# ROV_PWR_4inch.net
KiCad netlist of a schematic drawn in EAGLE
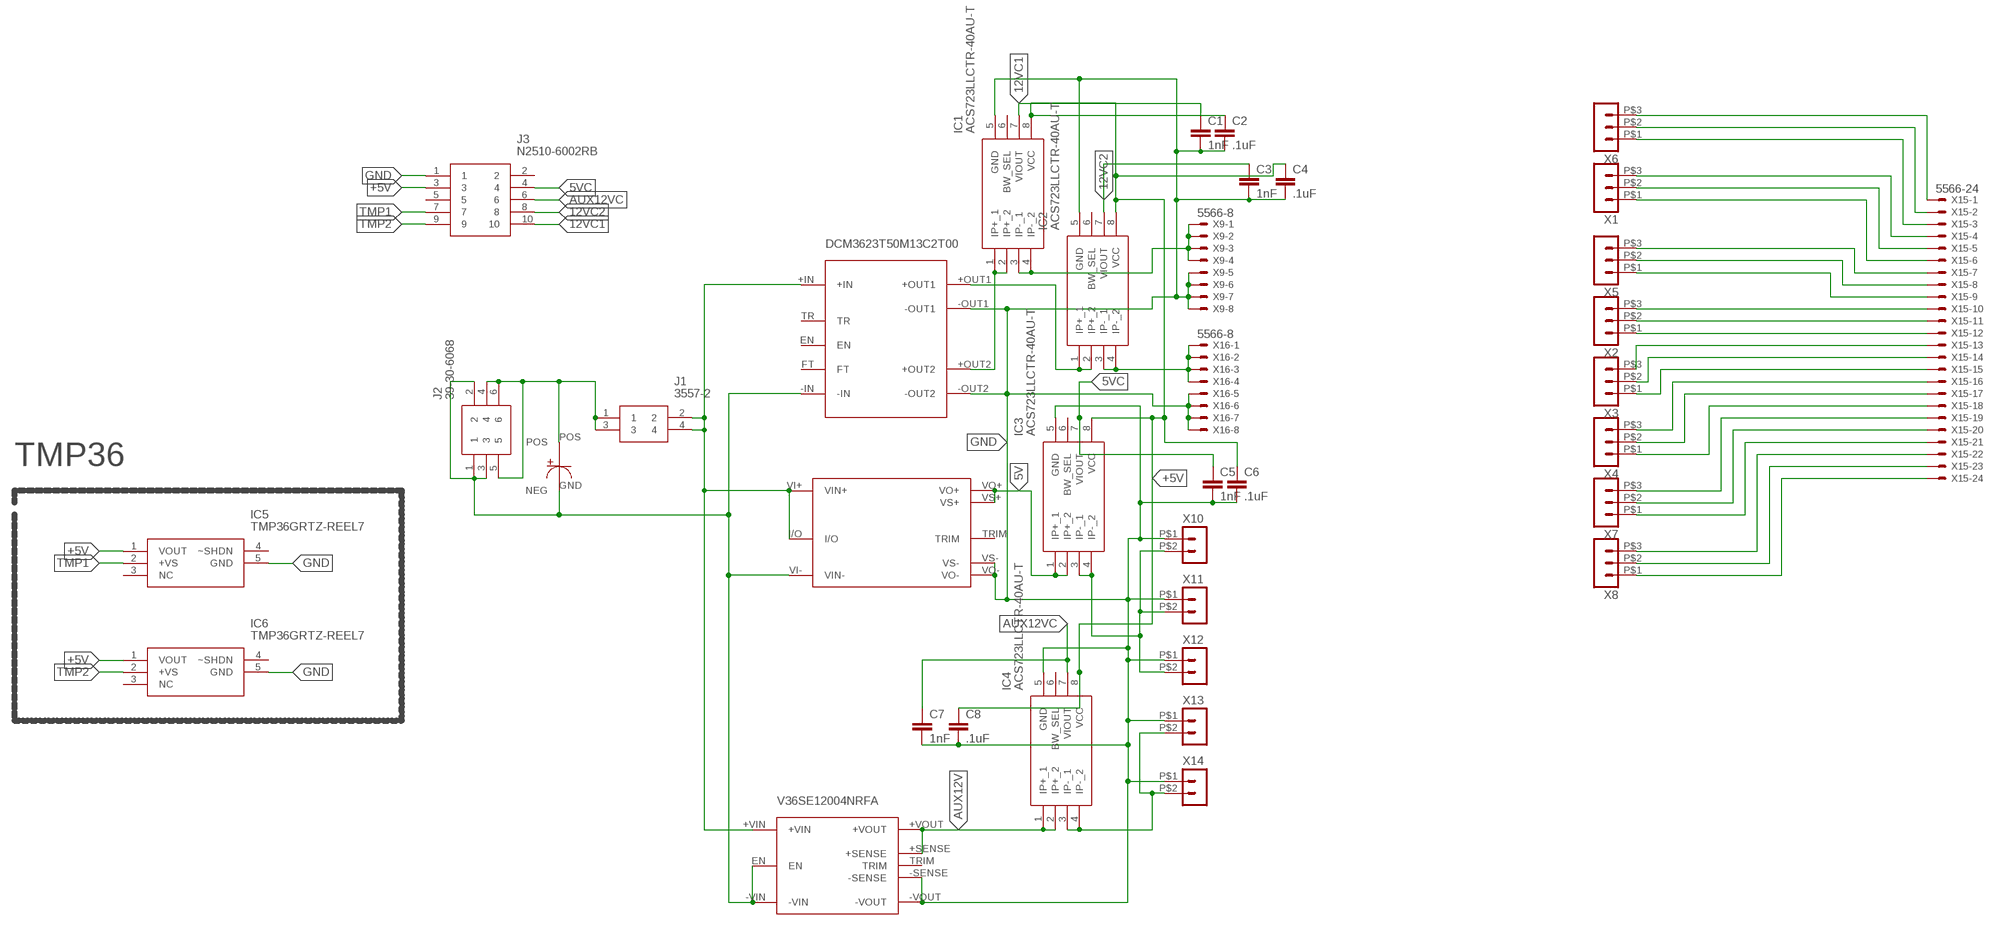
[diagram p0: schematic, sheet 1]

(export (version "E")
  (design (tool "Eeschema 10.0.6"))
  (components
    (comp (ref "C1")
      (value "1nF")
      (footprint "eagle-import:C0402")
      (libsource (lib "eagle-import") (part "C-EUC0402"))
    )
    (comp (ref "C2")
      (value ".1uF")
      (footprint "eagle-import:C0402")
      (libsource (lib "eagle-import") (part "C-EUC0402"))
    )
    (comp (ref "C3")
      (value "1nF")
      (footprint "eagle-import:C0402")
      (libsource (lib "eagle-import") (part "C-EUC0402"))
    )
    (comp (ref "C4")
      (value ".1uF")
      (footprint "eagle-import:C0402")
      (libsource (lib "eagle-import") (part "C-EUC0402"))
    )
    (comp (ref "C5")
      (value "1nF")
      (footprint "eagle-import:C0402")
      (libsource (lib "eagle-import") (part "C-EUC0402"))
    )
    (comp (ref "C6")
      (value ".1uF")
      (footprint "eagle-import:C0402")
      (libsource (lib "eagle-import") (part "C-EUC0402"))
    )
    (comp (ref "C7")
      (value "1nF")
      (footprint "eagle-import:C0402")
      (libsource (lib "eagle-import") (part "C-EUC0402"))
    )
    (comp (ref "C8")
      (value ".1uF")
      (footprint "eagle-import:C0402")
      (libsource (lib "eagle-import") (part "C-EUC0402"))
    )
    (comp (ref "IC1")
      (value "ACS723LLCTR-40AU-T")
      (footprint "eagle-import:SOT127P600X175-8N")
      (libsource (lib "eagle-import") (part "ACS723LLCTR-40AU-T"))
    )
    (comp (ref "IC2")
      (value "ACS723LLCTR-40AU-T")
      (footprint "eagle-import:SOT127P600X175-8N")
      (libsource (lib "eagle-import") (part "ACS723LLCTR-40AU-T"))
    )
    (comp (ref "IC3")
      (value "ACS723LLCTR-40AU-T")
      (footprint "eagle-import:SOT127P600X175-8N")
      (libsource (lib "eagle-import") (part "ACS723LLCTR-40AU-T"))
    )
    (comp (ref "IC4")
      (value "ACS723LLCTR-40AU-T")
      (footprint "eagle-import:SOT127P600X175-8N")
      (libsource (lib "eagle-import") (part "ACS723LLCTR-40AU-T"))
    )
    (comp (ref "IC5")
      (value "TMP36GRTZ-REEL7")
      (footprint "eagle-import:SOT95P280X145-5N")
      (fields (field (name "MOUSER_PART_NUMBER") "584-TMP36GRTZ-R7"))
      (libsource (lib "eagle-import") (part "TMP36GRTZ-REEL7"))
    )
    (comp (ref "IC6")
      (value "TMP36GRTZ-REEL7")
      (footprint "eagle-import:SOT95P280X145-5N")
      (fields (field (name "MOUSER_PART_NUMBER") "584-TMP36GRTZ-R7"))
      (libsource (lib "eagle-import") (part "TMP36GRTZ-REEL7"))
    )
    (comp (ref "J1")
      (value "3557-2")
      (footprint "eagle-import:3557-2")
      (fields (field (name "MOUSER_PART_NUMBER") "534-3557-2"))
      (libsource (lib "eagle-import") (part "3557-2"))
    )
    (comp (ref "J2")
      (value "39-30-6068")
      (footprint "eagle-import:39306068")
      (fields (field (name "MOUSER_PART_NUMBER") "538-39-30-6068"))
      (libsource (lib "eagle-import") (part "39-30-6068"))
    )
    (comp (ref "J3")
      (value "N2510-6002RB")
      (footprint "eagle-import:SHDR10W64P254_2X5_2002X859X100")
      (fields (field (name "MOUSER_PART_NUMBER") "517-N2510-6002RB"))
      (libsource (lib "eagle-import") (part "N2510-6002RB"))
    )
    (comp (ref "U$1")
      (value "DCM3623T50M13C2T00")
      (footprint "eagle-import:DCM3623T50M13C2T00")
      (libsource (lib "eagle-import") (part "DCM3623T50M13C2T00"))
    )
    (comp (ref "U$2")
      (value "KHHD006A0A41Z")
      (footprint "eagle-import:KHHD006A0A41Z")
      (libsource (lib "eagle-import") (part "KHHD006A0A41Z"))
    )
    (comp (ref "U$3")
      (value "V36SE12004NRFA")
      (footprint "eagle-import:V36SE12004NRFA")
      (libsource (lib "eagle-import") (part "V36SE12004NRFA"))
    )
    (comp (ref "U$4")
      (value "UBY1V222MHL")
      (footprint "eagle-import:UBY1V222MHL")
      (libsource (lib "eagle-import") (part "UBY1V222MHL"))
    )
    (comp (ref "X1")
      (value "HEADER_POS3_43650-0315")
      (footprint "eagle-import:43650-0315")
      (libsource (lib "eagle-import") (part "HEADER_POS3_?43650-0315"))
    )
    (comp (ref "X2")
      (value "HEADER_POS3_43650-0315")
      (footprint "eagle-import:43650-0315")
      (libsource (lib "eagle-import") (part "HEADER_POS3_?43650-0315"))
    )
    (comp (ref "X3")
      (value "HEADER_POS3_43650-0315")
      (footprint "eagle-import:43650-0315")
      (libsource (lib "eagle-import") (part "HEADER_POS3_?43650-0315"))
    )
    (comp (ref "X4")
      (value "HEADER_POS3_43650-0315")
      (footprint "eagle-import:43650-0315")
      (libsource (lib "eagle-import") (part "HEADER_POS3_?43650-0315"))
    )
    (comp (ref "X5")
      (value "HEADER_POS3_43650-0315")
      (footprint "eagle-import:43650-0315")
      (libsource (lib "eagle-import") (part "HEADER_POS3_?43650-0315"))
    )
    (comp (ref "X6")
      (value "HEADER_POS3_43650-0315")
      (footprint "eagle-import:43650-0315")
      (libsource (lib "eagle-import") (part "HEADER_POS3_?43650-0315"))
    )
    (comp (ref "X7")
      (value "HEADER_POS3_43650-0315")
      (footprint "eagle-import:43650-0315")
      (libsource (lib "eagle-import") (part "HEADER_POS3_?43650-0315"))
    )
    (comp (ref "X8")
      (value "HEADER_POS3_43650-0315")
      (footprint "eagle-import:43650-0315")
      (libsource (lib "eagle-import") (part "HEADER_POS3_?43650-0315"))
    )
    (comp (ref "X9")
      (value "5566-8")
      (footprint "eagle-import:5566-8")
      (fields (field (name "MF") "MOLEX"))
      (libsource (lib "eagle-import") (part "5566-8"))
    )
    (comp (ref "X10")
      (value "HEADER_POS2_44914-0201")
      (footprint "eagle-import:44914-0201")
      (libsource (lib "eagle-import") (part "HEADER_POS2_?44914-0201"))
    )
    (comp (ref "X11")
      (value "HEADER_POS2_44914-0201")
      (footprint "eagle-import:44914-0201")
      (libsource (lib "eagle-import") (part "HEADER_POS2_?44914-0201"))
    )
    (comp (ref "X12")
      (value "HEADER_POS2_44914-0201")
      (footprint "eagle-import:44914-0201")
      (libsource (lib "eagle-import") (part "HEADER_POS2_?44914-0201"))
    )
    (comp (ref "X13")
      (value "HEADER_POS2_44914-0201")
      (footprint "eagle-import:44914-0201")
      (libsource (lib "eagle-import") (part "HEADER_POS2_?44914-0201"))
    )
    (comp (ref "X14")
      (value "HEADER_POS2_44914-0201")
      (footprint "eagle-import:44914-0201")
      (libsource (lib "eagle-import") (part "HEADER_POS2_?44914-0201"))
    )
    (comp (ref "X15")
      (value "5566-24")
      (footprint "eagle-import:5566-24")
      (fields (field (name "MF") "MOLEX"))
      (libsource (lib "eagle-import") (part "5566-24"))
    )
    (comp (ref "X16")
      (value "5566-8")
      (footprint "eagle-import:5566-8")
      (fields (field (name "MF") "MOLEX"))
      (libsource (lib "eagle-import") (part "5566-8"))
    )
  )
  (nets
    (net (code "1") (name "+5V") (class "Default")
      (node (ref "C2") (pin "1") (pinfunction "1_1") (pintype "passive"))
      (node (ref "C4") (pin "1") (pinfunction "1_1") (pintype "passive"))
      (node (ref "C6") (pin "1") (pinfunction "1_1") (pintype "passive"))
      (node (ref "C8") (pin "1") (pinfunction "1_1") (pintype "passive"))
      (node (ref "IC1") (pin "8") (pinfunction "VCC_8") (pintype "power_in"))
      (node (ref "IC2") (pin "8") (pinfunction "VCC_8") (pintype "power_in"))
      (node (ref "IC3") (pin "8") (pinfunction "VCC_8") (pintype "power_in"))
      (node (ref "IC4") (pin "8") (pinfunction "VCC_8") (pintype "power_in"))
      (node (ref "IC5") (pin "1") (pinfunction "VOUT_1") (pintype "bidirectional"))
      (node (ref "IC6") (pin "1") (pinfunction "VOUT_1") (pintype "bidirectional"))
      (node (ref "J3") (pin "3") (pinfunction "3_3") (pintype "bidirectional"))
    )
    (net (code "2") (name "5V") (class "Default")
      (node (ref "IC3") (pin "1") (pinfunction "IP+_1_1") (pintype "input"))
      (node (ref "IC3") (pin "2") (pinfunction "IP+_2_2") (pintype "input"))
      (node (ref "U$2") (pin "VO+") (pinfunction "VO+_VO+") (pintype "bidirectional"))
      (node (ref "U$2") (pin "VS+") (pinfunction "VS+_VS+") (pintype "bidirectional"))
    )
    (net (code "3") (name "5VC") (class "Default")
      (node (ref "C5") (pin "1") (pinfunction "1_1") (pintype "passive"))
      (node (ref "IC3") (pin "7") (pinfunction "VIOUT_7") (pintype "output"))
      (node (ref "J3") (pin "4") (pinfunction "4_4") (pintype "bidirectional"))
    )
    (net (code "4") (name "12VC1") (class "Default")
      (node (ref "C1") (pin "1") (pinfunction "1_1") (pintype "passive"))
      (node (ref "IC1") (pin "7") (pinfunction "VIOUT_7") (pintype "output"))
      (node (ref "J3") (pin "10") (pinfunction "10_10") (pintype "bidirectional"))
    )
    (net (code "5") (name "12VC2") (class "Default")
      (node (ref "C3") (pin "1") (pinfunction "1_1") (pintype "passive"))
      (node (ref "IC2") (pin "7") (pinfunction "VIOUT_7") (pintype "output"))
      (node (ref "J3") (pin "8") (pinfunction "8_8") (pintype "bidirectional"))
    )
    (net (code "6") (name "AUX12V") (class "Default")
      (node (ref "IC4") (pin "1") (pinfunction "IP+_1_1") (pintype "input"))
      (node (ref "IC4") (pin "2") (pinfunction "IP+_2_2") (pintype "input"))
      (node (ref "U$3") (pin "+SENSE") (pinfunction "+SENSE_+SENSE") (pintype "bidirectional"))
      (node (ref "U$3") (pin "+VOUT") (pinfunction "+VOUT_+VOUT") (pintype "bidirectional"))
    )
    (net (code "7") (name "AUX12VC") (class "Default")
      (node (ref "C7") (pin "1") (pinfunction "1_1") (pintype "passive"))
      (node (ref "IC4") (pin "7") (pinfunction "VIOUT_7") (pintype "output"))
      (node (ref "J3") (pin "6") (pinfunction "6_6") (pintype "bidirectional"))
    )
    (net (code "8") (name "GND") (class "Default")
      (node (ref "C1") (pin "2") (pinfunction "2_2") (pintype "passive"))
      (node (ref "C2") (pin "2") (pinfunction "2_2") (pintype "passive"))
      (node (ref "C3") (pin "2") (pinfunction "2_2") (pintype "passive"))
      (node (ref "C4") (pin "2") (pinfunction "2_2") (pintype "passive"))
      (node (ref "C5") (pin "2") (pinfunction "2_2") (pintype "passive"))
      (node (ref "C6") (pin "2") (pinfunction "2_2") (pintype "passive"))
      (node (ref "C7") (pin "2") (pinfunction "2_2") (pintype "passive"))
      (node (ref "C8") (pin "2") (pinfunction "2_2") (pintype "passive"))
      (node (ref "IC1") (pin "5") (pinfunction "GND_5") (pintype "power_in"))
      (node (ref "IC2") (pin "5") (pinfunction "GND_5") (pintype "power_in"))
      (node (ref "IC3") (pin "5") (pinfunction "GND_5") (pintype "power_in"))
      (node (ref "IC4") (pin "5") (pinfunction "GND_5") (pintype "power_in"))
      (node (ref "IC5") (pin "5") (pinfunction "GND_5") (pintype "bidirectional"))
      (node (ref "IC6") (pin "5") (pinfunction "GND_5") (pintype "bidirectional"))
      (node (ref "J3") (pin "1") (pinfunction "1_1") (pintype "bidirectional"))
      (node (ref "U$1") (pin "-OUT1") (pinfunction "-OUT1_-OUT1") (pintype "bidirectional"))
      (node (ref "U$1") (pin "-OUT2") (pinfunction "-OUT2_-OUT2") (pintype "bidirectional"))
      (node (ref "U$2") (pin "VO-") (pinfunction "VO-_VO-") (pintype "bidirectional"))
      (node (ref "U$2") (pin "VS-") (pinfunction "VS-_VS-") (pintype "bidirectional"))
      (node (ref "U$3") (pin "-SENSE") (pinfunction "-SENSE_-SENSE") (pintype "bidirectional"))
      (node (ref "U$3") (pin "-VOUT") (pinfunction "-VOUT_-VOUT") (pintype "bidirectional"))
      (node (ref "X10") (pin "P$1") (pinfunction "1_P$1") (pintype "passive"))
      (node (ref "X11") (pin "P$1") (pinfunction "1_P$1") (pintype "passive"))
      (node (ref "X12") (pin "P$1") (pinfunction "1_P$1") (pintype "passive"))
      (node (ref "X13") (pin "P$1") (pinfunction "1_P$1") (pintype "passive"))
      (node (ref "X14") (pin "P$1") (pinfunction "1_P$1") (pintype "passive"))
      (node (ref "X16") (pin "5") (pinfunction "S_5") (pintype "passive"))
      (node (ref "X16") (pin "6") (pinfunction "S_6") (pintype "passive"))
      (node (ref "X16") (pin "7") (pinfunction "S_7") (pintype "passive"))
      (node (ref "X16") (pin "8") (pinfunction "S_8") (pintype "passive"))
      (node (ref "X9") (pin "5") (pinfunction "S_5") (pintype "passive"))
      (node (ref "X9") (pin "6") (pinfunction "S_6") (pintype "passive"))
      (node (ref "X9") (pin "7") (pinfunction "S_7") (pintype "passive"))
      (node (ref "X9") (pin "8") (pinfunction "S_8") (pintype "passive"))
    )
    (net (code "9") (name "Net-(IC1-IP+_1)") (class "Default")
      (node (ref "IC1") (pin "1") (pinfunction "IP+_1_1") (pintype "input"))
      (node (ref "IC1") (pin "2") (pinfunction "IP+_2_2") (pintype "input"))
      (node (ref "U$1") (pin "+OUT2") (pinfunction "+OUT2_+OUT2") (pintype "bidirectional"))
    )
    (net (code "10") (name "Net-(IC1-IP-_1)") (class "Default")
      (node (ref "IC1") (pin "3") (pinfunction "IP-_1_3") (pintype "input"))
      (node (ref "IC1") (pin "4") (pinfunction "IP-_2_4") (pintype "input"))
      (node (ref "X9") (pin "1") (pinfunction "S_1") (pintype "passive"))
      (node (ref "X9") (pin "2") (pinfunction "S_2") (pintype "passive"))
      (node (ref "X9") (pin "3") (pinfunction "S_3") (pintype "passive"))
      (node (ref "X9") (pin "4") (pinfunction "S_4") (pintype "passive"))
    )
    (net (code "11") (name "Net-(IC2-IP+_1)") (class "Default")
      (node (ref "IC2") (pin "1") (pinfunction "IP+_1_1") (pintype "input"))
      (node (ref "IC2") (pin "2") (pinfunction "IP+_2_2") (pintype "input"))
      (node (ref "U$1") (pin "+OUT1") (pinfunction "+OUT1_+OUT1") (pintype "bidirectional"))
    )
    (net (code "12") (name "Net-(IC2-IP-_1)") (class "Default")
      (node (ref "IC2") (pin "3") (pinfunction "IP-_1_3") (pintype "input"))
      (node (ref "IC2") (pin "4") (pinfunction "IP-_2_4") (pintype "input"))
      (node (ref "X16") (pin "1") (pinfunction "S_1") (pintype "passive"))
      (node (ref "X16") (pin "2") (pinfunction "S_2") (pintype "passive"))
      (node (ref "X16") (pin "3") (pinfunction "S_3") (pintype "passive"))
      (node (ref "X16") (pin "4") (pinfunction "S_4") (pintype "passive"))
    )
    (net (code "13") (name "Net-(IC3-IP-_1)") (class "Default")
      (node (ref "IC3") (pin "3") (pinfunction "IP-_1_3") (pintype "input"))
      (node (ref "IC3") (pin "4") (pinfunction "IP-_2_4") (pintype "input"))
      (node (ref "X10") (pin "P$2") (pinfunction "2_P$2") (pintype "passive"))
      (node (ref "X11") (pin "P$2") (pinfunction "2_P$2") (pintype "passive"))
      (node (ref "X12") (pin "P$2") (pinfunction "2_P$2") (pintype "passive"))
    )
    (net (code "14") (name "Net-(IC4-IP-_1)") (class "Default")
      (node (ref "IC4") (pin "3") (pinfunction "IP-_1_3") (pintype "input"))
      (node (ref "IC4") (pin "4") (pinfunction "IP-_2_4") (pintype "input"))
      (node (ref "X13") (pin "P$2") (pinfunction "2_P$2") (pintype "passive"))
      (node (ref "X14") (pin "P$2") (pinfunction "2_P$2") (pintype "passive"))
    )
    (net (code "15") (name "Net-(J1-Pad1)") (class "Default")
      (node (ref "J1") (pin "1") (pinfunction "1_1") (pintype "bidirectional"))
      (node (ref "J1") (pin "3") (pinfunction "3_3") (pintype "bidirectional"))
      (node (ref "J2") (pin "4") (pinfunction "4_4") (pintype "bidirectional"))
      (node (ref "J2") (pin "5") (pinfunction "5_5") (pintype "bidirectional"))
      (node (ref "J2") (pin "6") (pinfunction "6_6") (pintype "bidirectional"))
      (node (ref "U$4") (pin "POS") (pinfunction "POS_POS") (pintype "bidirectional"))
    )
    (net (code "16") (name "Net-(U$2-VIN+)") (class "Default")
      (node (ref "J1") (pin "2") (pinfunction "2_2") (pintype "bidirectional"))
      (node (ref "J1") (pin "4") (pinfunction "4_4") (pintype "bidirectional"))
      (node (ref "U$1") (pin "+IN") (pinfunction "+IN_+IN") (pintype "bidirectional"))
      (node (ref "U$2") (pin "I/O") (pinfunction "I/O_I/O") (pintype "bidirectional"))
      (node (ref "U$2") (pin "VI+") (pinfunction "VIN+_VI+") (pintype "bidirectional"))
      (node (ref "U$3") (pin "+VIN") (pinfunction "+VIN_+VIN") (pintype "bidirectional"))
    )
    (net (code "17") (name "Net-(U$2-VIN-)") (class "Default")
      (node (ref "J2") (pin "1") (pinfunction "1_1") (pintype "bidirectional"))
      (node (ref "J2") (pin "2") (pinfunction "2_2") (pintype "bidirectional"))
      (node (ref "J2") (pin "3") (pinfunction "3_3") (pintype "bidirectional"))
      (node (ref "U$1") (pin "-IN") (pinfunction "-IN_-IN") (pintype "bidirectional"))
      (node (ref "U$2") (pin "VI-") (pinfunction "VIN-_VI-") (pintype "bidirectional"))
      (node (ref "U$3") (pin "-VIN") (pinfunction "-VIN_-VIN") (pintype "bidirectional"))
      (node (ref "U$3") (pin "EN") (pinfunction "EN_EN") (pintype "bidirectional"))
      (node (ref "U$4") (pin "GND") (pinfunction "NEG_GND") (pintype "bidirectional"))
    )
    (net (code "18") (name "Net-(X1-1)") (class "Default")
      (node (ref "X1") (pin "P$1") (pinfunction "1_P$1") (pintype "passive"))
      (node (ref "X15") (pin "6") (pinfunction "S_6") (pintype "passive"))
    )
    (net (code "19") (name "Net-(X1-2)") (class "Default")
      (node (ref "X1") (pin "P$2") (pinfunction "2_P$2") (pintype "passive"))
      (node (ref "X15") (pin "5") (pinfunction "S_5") (pintype "passive"))
    )
    (net (code "20") (name "Net-(X1-3)") (class "Default")
      (node (ref "X1") (pin "P$3") (pinfunction "3_P$3") (pintype "passive"))
      (node (ref "X15") (pin "4") (pinfunction "S_4") (pintype "passive"))
    )
    (net (code "21") (name "Net-(X15A-S)") (class "Default")
      (node (ref "X15") (pin "1") (pinfunction "S_1") (pintype "passive"))
      (node (ref "X6") (pin "P$3") (pinfunction "3_P$3") (pintype "passive"))
    )
    (net (code "22") (name "Net-(X15B-S)") (class "Default")
      (node (ref "X15") (pin "10") (pinfunction "S_10") (pintype "passive"))
      (node (ref "X2") (pin "P$3") (pinfunction "3_P$3") (pintype "passive"))
    )
    (net (code "23") (name "Net-(X15C-S)") (class "Default")
      (node (ref "X15") (pin "11") (pinfunction "S_11") (pintype "passive"))
      (node (ref "X2") (pin "P$2") (pinfunction "2_P$2") (pintype "passive"))
    )
    (net (code "24") (name "Net-(X15D-S)") (class "Default")
      (node (ref "X15") (pin "12") (pinfunction "S_12") (pintype "passive"))
      (node (ref "X2") (pin "P$1") (pinfunction "1_P$1") (pintype "passive"))
    )
    (net (code "25") (name "Net-(X15E-S)") (class "Default")
      (node (ref "X15") (pin "13") (pinfunction "S_13") (pintype "passive"))
      (node (ref "X3") (pin "P$3") (pinfunction "3_P$3") (pintype "passive"))
    )
    (net (code "26") (name "Net-(X15F-S)") (class "Default")
      (node (ref "X15") (pin "14") (pinfunction "S_14") (pintype "passive"))
      (node (ref "X3") (pin "P$2") (pinfunction "2_P$2") (pintype "passive"))
    )
    (net (code "27") (name "Net-(X15G-S)") (class "Default")
      (node (ref "X15") (pin "15") (pinfunction "S_15") (pintype "passive"))
      (node (ref "X3") (pin "P$1") (pinfunction "1_P$1") (pintype "passive"))
    )
    (net (code "28") (name "Net-(X15H-S)") (class "Default")
      (node (ref "X15") (pin "16") (pinfunction "S_16") (pintype "passive"))
      (node (ref "X4") (pin "P$3") (pinfunction "3_P$3") (pintype "passive"))
    )
    (net (code "29") (name "Net-(X15I-S)") (class "Default")
      (node (ref "X15") (pin "17") (pinfunction "S_17") (pintype "passive"))
      (node (ref "X4") (pin "P$2") (pinfunction "2_P$2") (pintype "passive"))
    )
    (net (code "30") (name "Net-(X15J-S)") (class "Default")
      (node (ref "X15") (pin "18") (pinfunction "S_18") (pintype "passive"))
      (node (ref "X4") (pin "P$1") (pinfunction "1_P$1") (pintype "passive"))
    )
    (net (code "31") (name "Net-(X15K-S)") (class "Default")
      (node (ref "X15") (pin "19") (pinfunction "S_19") (pintype "passive"))
      (node (ref "X7") (pin "P$3") (pinfunction "3_P$3") (pintype "passive"))
    )
    (net (code "32") (name "Net-(X15L-S)") (class "Default")
      (node (ref "X15") (pin "2") (pinfunction "S_2") (pintype "passive"))
      (node (ref "X6") (pin "P$2") (pinfunction "2_P$2") (pintype "passive"))
    )
    (net (code "33") (name "Net-(X15M-S)") (class "Default")
      (node (ref "X15") (pin "20") (pinfunction "S_20") (pintype "passive"))
      (node (ref "X7") (pin "P$2") (pinfunction "2_P$2") (pintype "passive"))
    )
    (net (code "34") (name "Net-(X15N-S)") (class "Default")
      (node (ref "X15") (pin "21") (pinfunction "S_21") (pintype "passive"))
      (node (ref "X7") (pin "P$1") (pinfunction "1_P$1") (pintype "passive"))
    )
    (net (code "35") (name "Net-(X15O-S)") (class "Default")
      (node (ref "X15") (pin "22") (pinfunction "S_22") (pintype "passive"))
      (node (ref "X8") (pin "P$3") (pinfunction "3_P$3") (pintype "passive"))
    )
    (net (code "36") (name "Net-(X15P-S)") (class "Default")
      (node (ref "X15") (pin "23") (pinfunction "S_23") (pintype "passive"))
      (node (ref "X8") (pin "P$2") (pinfunction "2_P$2") (pintype "passive"))
    )
    (net (code "37") (name "Net-(X15Q-S)") (class "Default")
      (node (ref "X15") (pin "24") (pinfunction "S_24") (pintype "passive"))
      (node (ref "X8") (pin "P$1") (pinfunction "1_P$1") (pintype "passive"))
    )
    (net (code "38") (name "Net-(X15R-S)") (class "Default")
      (node (ref "X15") (pin "3") (pinfunction "S_3") (pintype "passive"))
      (node (ref "X6") (pin "P$1") (pinfunction "1_P$1") (pintype "passive"))
    )
    (net (code "39") (name "Net-(X15V-S)") (class "Default")
      (node (ref "X15") (pin "7") (pinfunction "S_7") (pintype "passive"))
      (node (ref "X5") (pin "P$3") (pinfunction "3_P$3") (pintype "passive"))
    )
    (net (code "40") (name "Net-(X15W-S)") (class "Default")
      (node (ref "X15") (pin "8") (pinfunction "S_8") (pintype "passive"))
      (node (ref "X5") (pin "P$2") (pinfunction "2_P$2") (pintype "passive"))
    )
    (net (code "41") (name "Net-(X15X-S)") (class "Default")
      (node (ref "X15") (pin "9") (pinfunction "S_9") (pintype "passive"))
      (node (ref "X5") (pin "P$1") (pinfunction "1_P$1") (pintype "passive"))
    )
    (net (code "42") (name "TMP1") (class "Default")
      (node (ref "IC5") (pin "2") (pinfunction "+VS_2") (pintype "bidirectional"))
      (node (ref "J3") (pin "7") (pinfunction "7_7") (pintype "bidirectional"))
    )
    (net (code "43") (name "TMP2") (class "Default")
      (node (ref "IC6") (pin "2") (pinfunction "+VS_2") (pintype "bidirectional"))
      (node (ref "J3") (pin "9") (pinfunction "9_9") (pintype "bidirectional"))
    )
    (net (code "44") (name "unconnected-(IC1-BW_SEL-Pad6)") (class "Default")
      (node (ref "IC1") (pin "6") (pinfunction "BW_SEL_6") (pintype "input"))
    )
    (net (code "45") (name "unconnected-(IC2-BW_SEL-Pad6)") (class "Default")
      (node (ref "IC2") (pin "6") (pinfunction "BW_SEL_6") (pintype "input"))
    )
    (net (code "46") (name "unconnected-(IC3-BW_SEL-Pad6)") (class "Default")
      (node (ref "IC3") (pin "6") (pinfunction "BW_SEL_6") (pintype "input"))
    )
    (net (code "47") (name "unconnected-(IC4-BW_SEL-Pad6)") (class "Default")
      (node (ref "IC4") (pin "6") (pinfunction "BW_SEL_6") (pintype "input"))
    )
    (net (code "48") (name "unconnected-(IC5-NC-Pad3)") (class "Default")
      (node (ref "IC5") (pin "3") (pinfunction "NC_3") (pintype "no_connect"))
    )
    (net (code "49") (name "unconnected-(IC5-~{SHDN}-Pad4)") (class "Default")
      (node (ref "IC5") (pin "4") (pinfunction "~{SHDN}_4") (pintype "bidirectional"))
    )
    (net (code "50") (name "unconnected-(IC6-NC-Pad3)") (class "Default")
      (node (ref "IC6") (pin "3") (pinfunction "NC_3") (pintype "no_connect"))
    )
    (net (code "51") (name "unconnected-(IC6-~{SHDN}-Pad4)") (class "Default")
      (node (ref "IC6") (pin "4") (pinfunction "~{SHDN}_4") (pintype "bidirectional"))
    )
    (net (code "52") (name "unconnected-(J3-Pad2)") (class "Default")
      (node (ref "J3") (pin "2") (pinfunction "2_2") (pintype "bidirectional"))
    )
    (net (code "53") (name "unconnected-(J3-Pad5)") (class "Default")
      (node (ref "J3") (pin "5") (pinfunction "5_5") (pintype "bidirectional"))
    )
    (net (code "54") (name "unconnected-(U$1-PadEN)") (class "Default")
      (node (ref "U$1") (pin "EN") (pinfunction "EN_EN") (pintype "bidirectional"))
    )
    (net (code "55") (name "unconnected-(U$1-PadFT)") (class "Default")
      (node (ref "U$1") (pin "FT") (pinfunction "FT_FT") (pintype "bidirectional"))
    )
    (net (code "56") (name "unconnected-(U$1-PadTR)") (class "Default")
      (node (ref "U$1") (pin "TR") (pinfunction "TR_TR") (pintype "bidirectional"))
    )
    (net (code "57") (name "unconnected-(U$2-PadTRIM)") (class "Default")
      (node (ref "U$2") (pin "TRIM") (pinfunction "TRIM_TRIM") (pintype "bidirectional"))
    )
    (net (code "58") (name "unconnected-(U$3-PadTRIM)") (class "Default")
      (node (ref "U$3") (pin "TRIM") (pinfunction "TRIM_TRIM") (pintype "bidirectional"))
    )
  )
)
